# SCH_18221-card_2024-06-19.net
KiCad netlist of a schematic drawn in EasyEDA
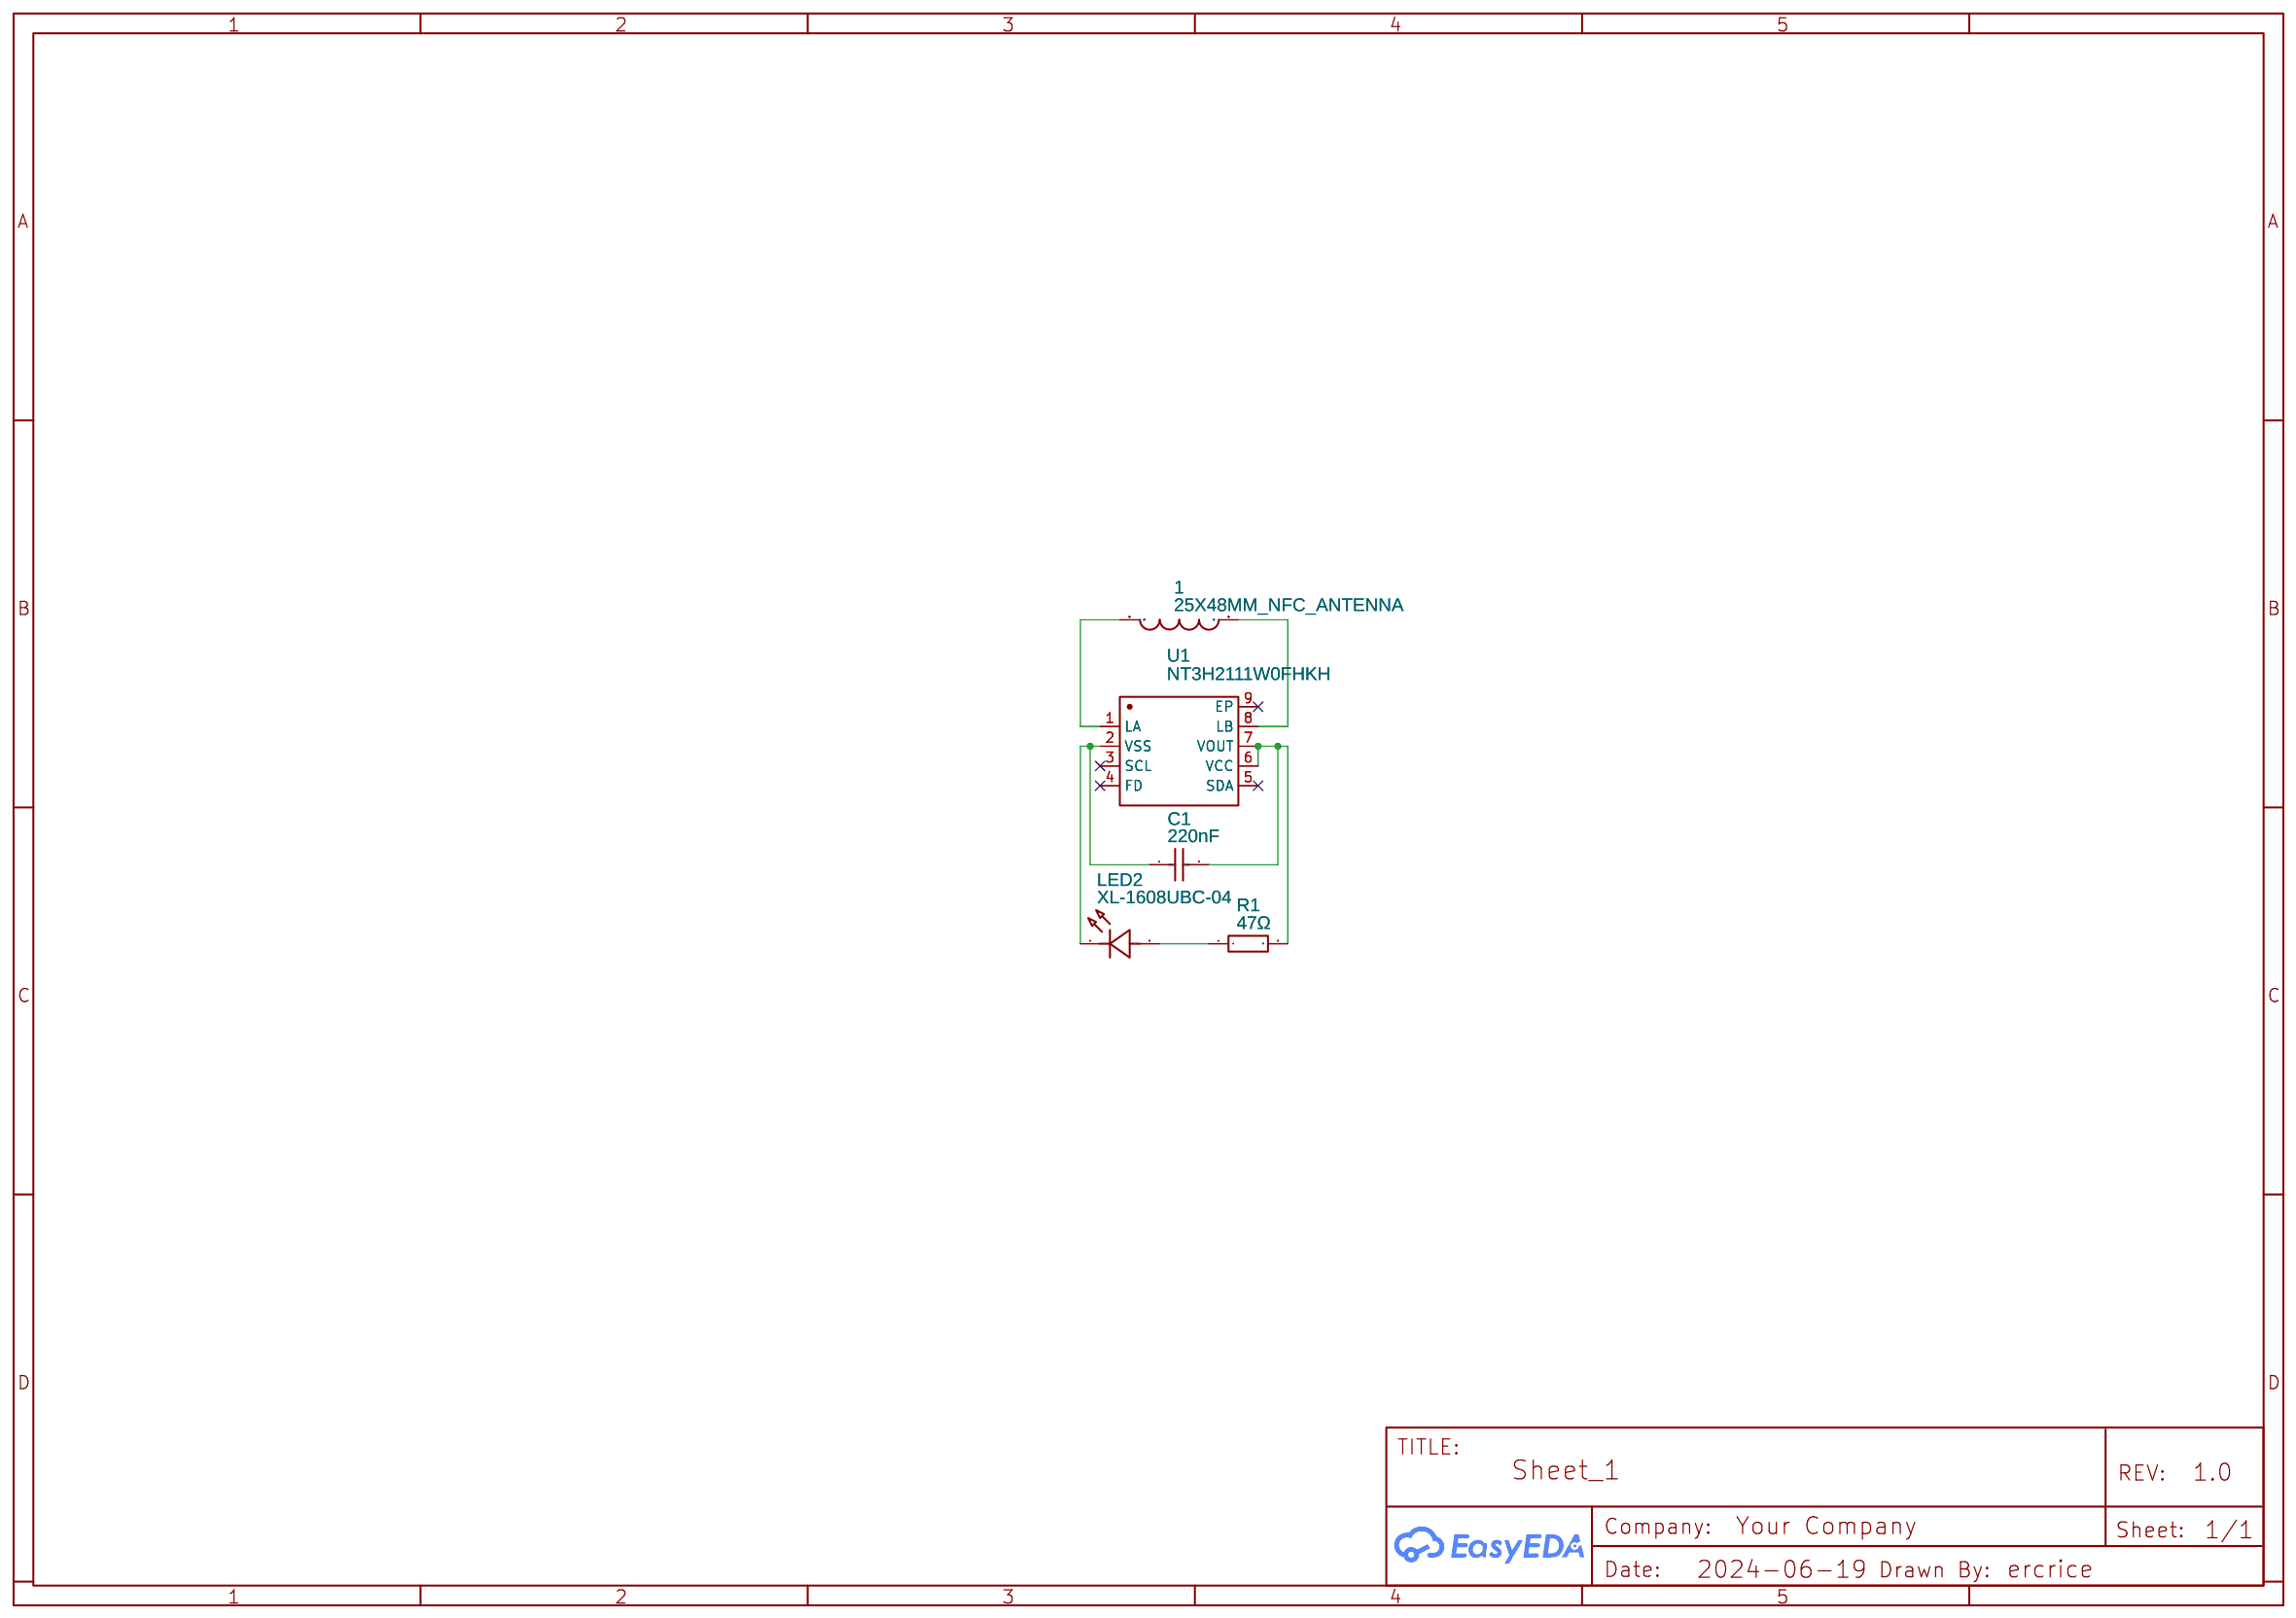
[diagram p0: schematic sheet]

(export (version "E")
  (design (tool "Eeschema 10.0.6"))
  (components
    (comp (ref "1")
      (value "25X48MM_NFC_ANTENNA")
      (libsource (lib "") (part "25X48MM_NFC_ANTENNA_EXPOSED_COPPER"))
    )
    (comp (ref "C1")
      (value "220nF")
      (fields
        (field (name "Manufacturer Part") "CL10B224KA8NNNC")
        (field (name "Manufacturer") "SAMSUNG(三星)")
      )
      (libsource (lib "") (part "CL10B224KA8NNNC"))
    )
    (comp (ref "LED2")
      (value "XL-1608UBC-04")
      (fields (field (name "Manufacturer") "XINGLIGHT(成兴光)"))
      (libsource (lib "") (part "XL-1608UBC-04"))
    )
    (comp (ref "R1")
      (value "47Ω")
      (fields
        (field (name "Manufacturer Part") "0603WAF470JT5E")
        (field (name "Manufacturer") "UNI-ROYAL(厚声)")
      )
      (libsource (lib "") (part "0603WAF470JT5E"))
    )
    (comp (ref "U1")
      (value "NT3H2111W0FHKH")
      (fields (field (name "Manufacturer") "NXP(恩智浦)"))
      (libsource (lib "") (part "NT3H2111W0FHKH"))
    )
  )
  (nets
    (net (code "1") (name "Net-(LED2-A)") (class "Default")
      (node (ref "LED2") (pin "2") (pinfunction "A_2") (pintype "unspecified"))
      (node (ref "R1") (pin "1") (pinfunction "1_1") (pintype "input"))
    )
    (net (code "2") (name "Net-(LED2-K)") (class "Default")
      (node (ref "C1") (pin "1") (pinfunction "1_1") (pintype "input"))
      (node (ref "LED2") (pin "1") (pinfunction "K_1") (pintype "unspecified"))
      (node (ref "U1") (pin "2") (pinfunction "VSS_2") (pintype "unspecified"))
    )
    (net (code "3") (name "Net-(U1-LA)") (class "Default")
      (node (ref "1") (pin "P$2") (pinfunction "P$2_P$2") (pintype "bidirectional"))
      (node (ref "U1") (pin "1") (pinfunction "LA_1") (pintype "unspecified"))
    )
    (net (code "4") (name "Net-(U1-LB)") (class "Default")
      (node (ref "1") (pin "P$1") (pinfunction "P$1_P$1") (pintype "bidirectional"))
      (node (ref "U1") (pin "8") (pinfunction "LB_8") (pintype "unspecified"))
    )
    (net (code "5") (name "Net-(U1-VCC)") (class "Default")
      (node (ref "C1") (pin "2") (pinfunction "2_2") (pintype "input"))
      (node (ref "R1") (pin "2") (pinfunction "2_2") (pintype "input"))
      (node (ref "U1") (pin "6") (pinfunction "VCC_6") (pintype "unspecified"))
      (node (ref "U1") (pin "7") (pinfunction "VOUT_7") (pintype "unspecified"))
    )
    (net (code "6") (name "unconnected-(U1-EP-Pad9)") (class "Default")
      (node (ref "U1") (pin "9") (pinfunction "EP_9") (pintype "unspecified+no_connect"))
    )
    (net (code "7") (name "unconnected-(U1-FD-Pad4)") (class "Default")
      (node (ref "U1") (pin "4") (pinfunction "FD_4") (pintype "unspecified+no_connect"))
    )
    (net (code "8") (name "unconnected-(U1-SCL-Pad3)") (class "Default")
      (node (ref "U1") (pin "3") (pinfunction "SCL_3") (pintype "unspecified+no_connect"))
    )
    (net (code "9") (name "unconnected-(U1-SDA-Pad5)") (class "Default")
      (node (ref "U1") (pin "5") (pinfunction "SDA_5") (pintype "unspecified+no_connect"))
    )
  )
)
